# MCU_block.net
KiCad netlist of a schematic drawn in Altium Designer
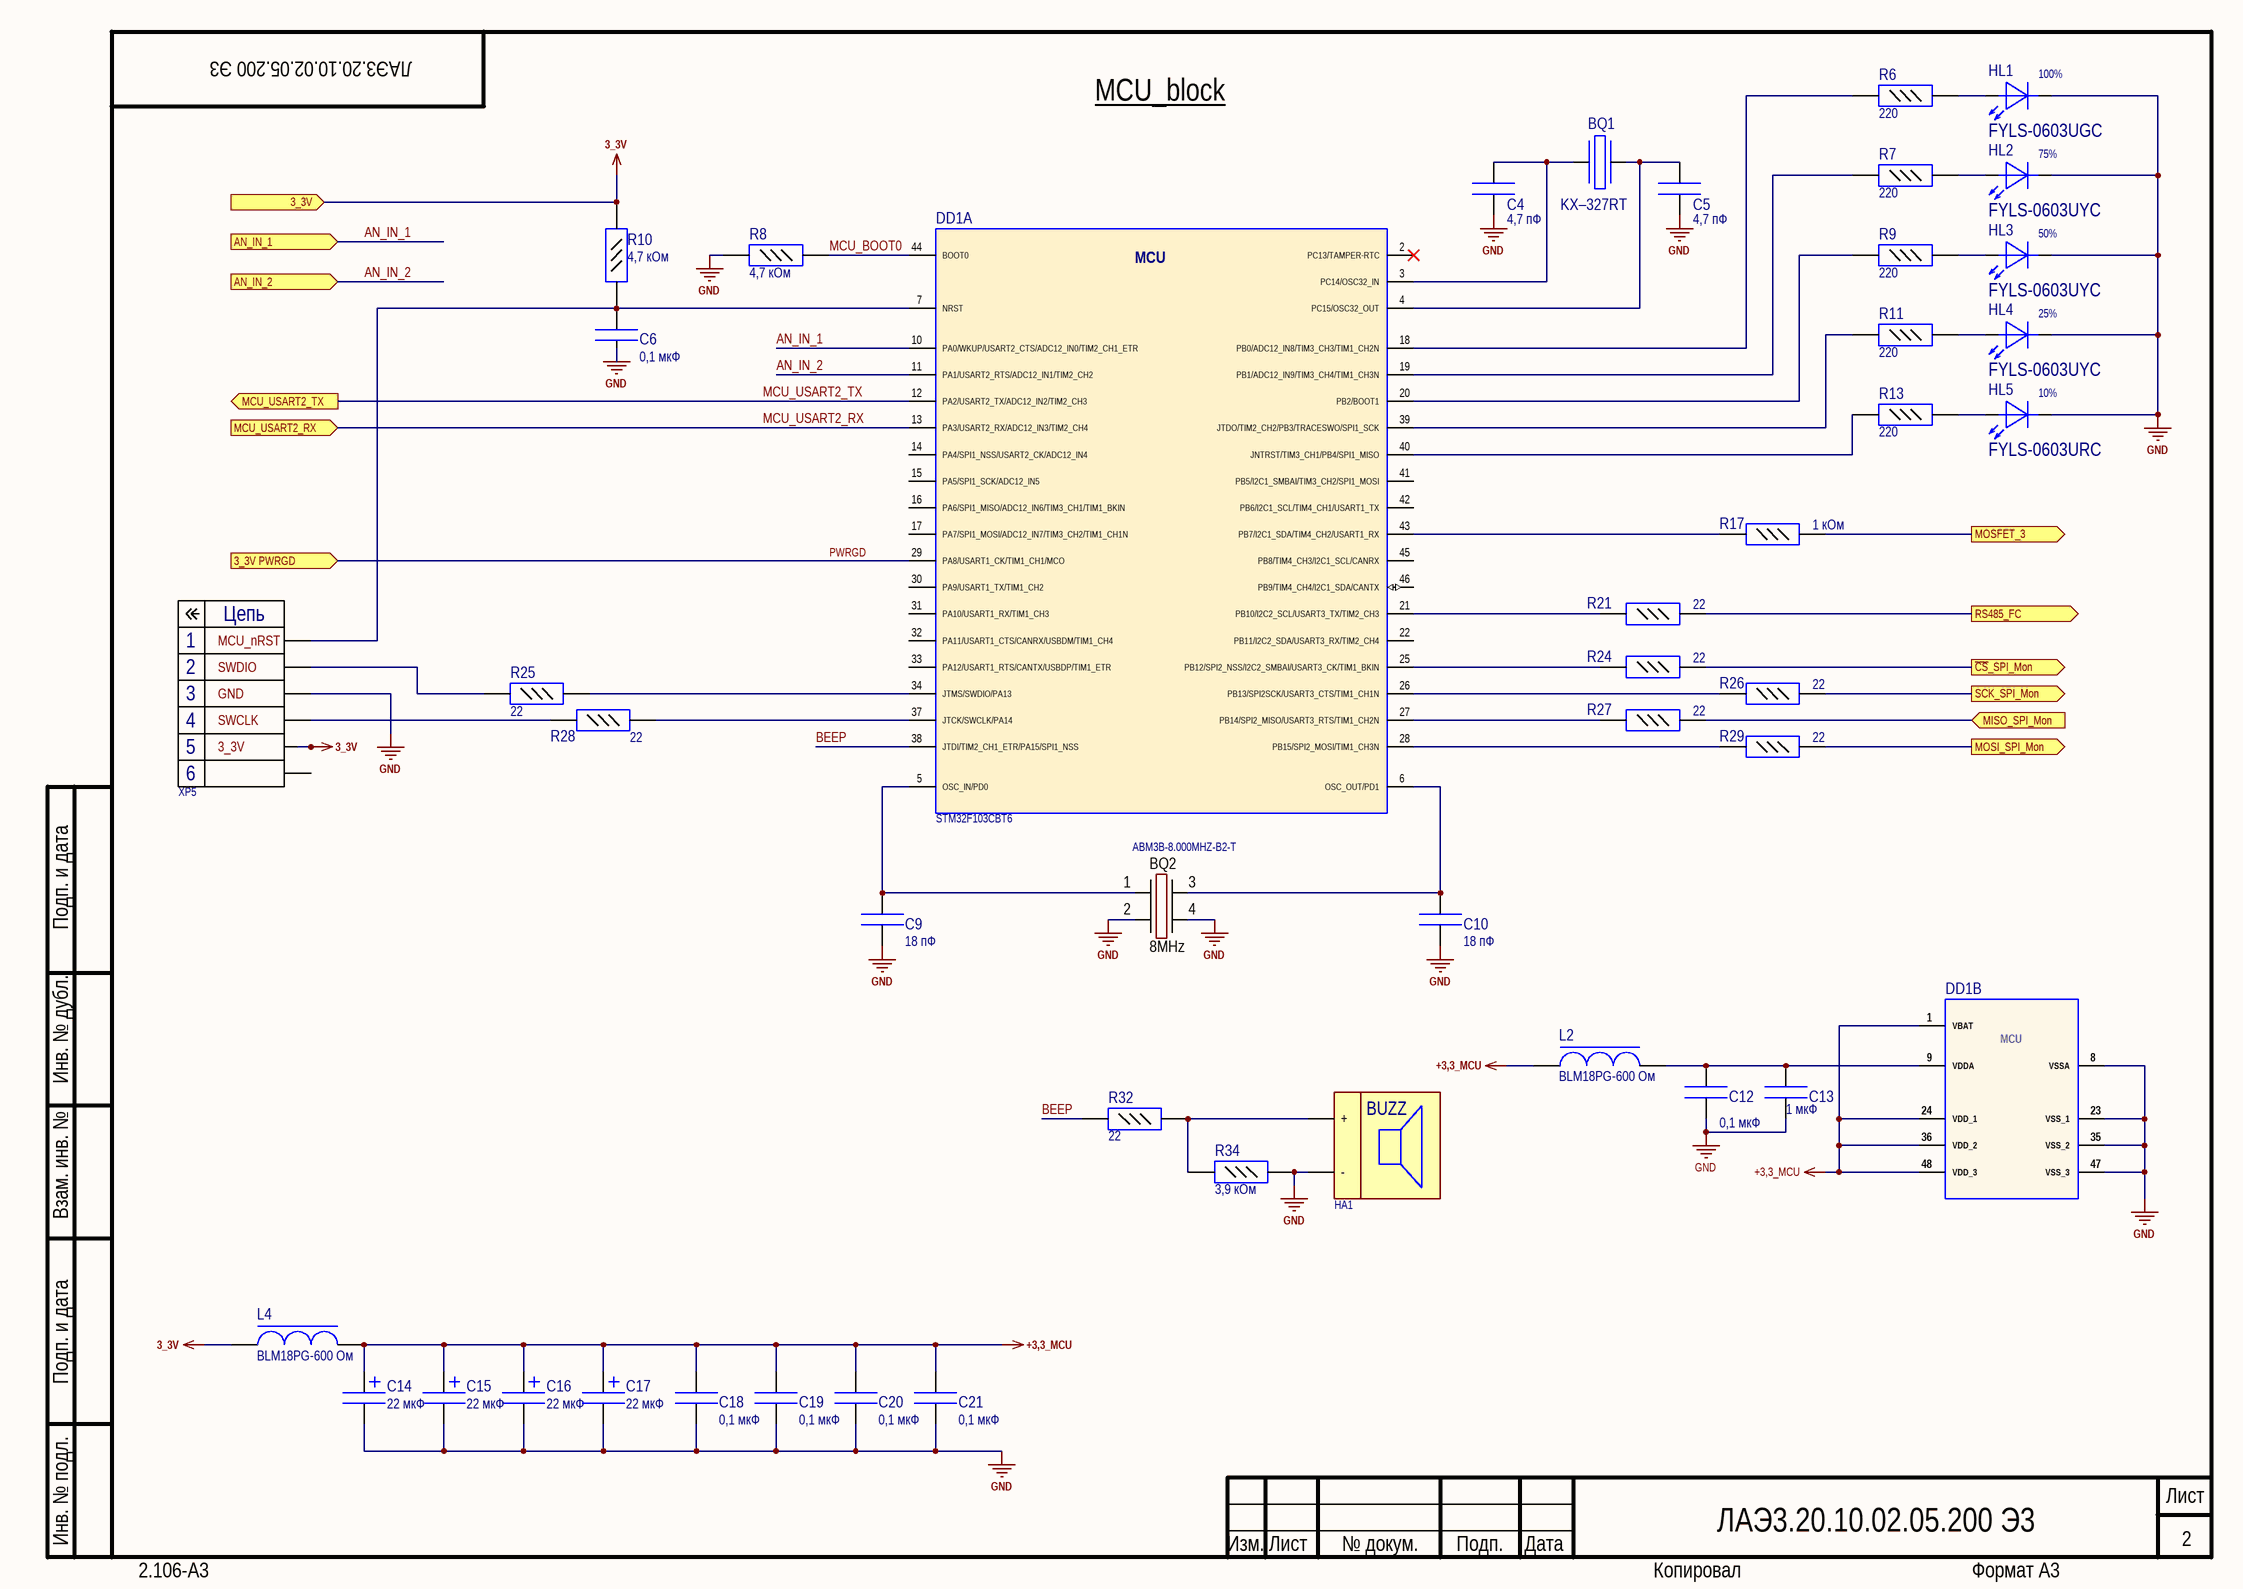
[diagram p0: MCU_block.SchDoc]

(export (version "E")
  (design (tool "Eeschema 10.0.6"))
  (components
    (comp (ref "BQ1")
      (value "KX–327RT")
      (footprint "KX–327RT")
      (description "Чип резонатор 32.768 кГц")
      (libsource (lib "Резонаторы") (part "KX–327RT"))
    )
    (comp (ref "BQ2")
      (value "ABM3B-8.000MHZ-B2-T")
      (footprint "OSC: 5032")
      (fields
        (field (name "MANUFACTURER") "Diodes Incorporated")
        (field (name "PARTNUMBER") "FY1000009")
        (field (name "VALUEMANUFACTURERPARTNUMBER") "Crystal, 8MHz, 20pF, ±30ppm, case 5032, -40...+85°C")
        (field (name "FREQUENCY") "8MHz")
        (field (name "SUPPLIER PART NUMBER 1") "ABM3B-8.000MHZ-B2-T")
      )
      (libsource (lib "Oscilator") (part "Crystal_5032"))
    )
    (comp (ref "C4")
      (value "4,7 пФ")
      (footprint "CC0603")
      (description "Чип конденсатор керамический")
      (fields (field (name "Comment") "CC0603-X5R-4,7 пФ-20%-10В"))
      (libsource (lib "Конденсаторы") (part "CC0603-X5R-#-20%-10В"))
    )
    (comp (ref "C5")
      (value "4,7 пФ")
      (footprint "CC0603")
      (description "Чип конденсатор керамический")
      (fields (field (name "Comment") "CC0603-X5R-4,7 пФ-20%-10В"))
      (libsource (lib "Конденсаторы") (part "CC0603-X5R-#-20%-10В"))
    )
    (comp (ref "C6")
      (value "0,1 мкФ")
      (footprint "CC0603")
      (description "Чип конденсатор керамический")
      (fields (field (name "Comment") "CC0603-X5R-0,1 мкФ-20%-10В"))
      (libsource (lib "Конденсаторы") (part "CC0603-X5R-#-20%-10В"))
    )
    (comp (ref "C9")
      (value "18 пФ")
      (footprint "CC0603")
      (description "Чип конденсатор керамический")
      (fields (field (name "Comment") "CC0603-X5R-18 пФ-20%-10В"))
      (libsource (lib "Конденсаторы") (part "CC0603-X5R-#-20%-10В"))
    )
    (comp (ref "C10")
      (value "18 пФ")
      (footprint "CC0603")
      (description "Чип конденсатор керамический")
      (fields (field (name "Comment") "CC0603-X5R-18 пФ-20%-10В"))
      (libsource (lib "Конденсаторы") (part "CC0603-X5R-#-20%-10В"))
    )
    (comp (ref "C12")
      (value "0,1 мкФ")
      (footprint "CC0603")
      (description "Чип конденсатор керамический")
      (fields (field (name "Comment") "CC0603-X5R-0,1 мкФ-20%-10В"))
      (libsource (lib "Конденсаторы") (part "CC0603-X5R-#-20%-10В"))
    )
    (comp (ref "C13")
      (value "1 мкФ")
      (footprint "CC0603")
      (description "Чип конденсатор керамический")
      (fields (field (name "Comment") "CC0603-X5R-1 мкФ-20%-10В"))
      (libsource (lib "Конденсаторы") (part "CC0603-X5R-#-20%-10В"))
    )
    (comp (ref "C14")
      (value "22 мкФ")
      (footprint "CT-C")
      (description "Чип конденсатор  танталовый")
      (fields (field (name "PARTNUMBER") "593D226X9016C2TE3") (field (name "Comment") "CT-10V-22uF-±20%-C"))
      (libsource (lib "Конденсаторы") (part "CT-10V-#-±20%-C"))
    )
    (comp (ref "C15")
      (value "22 мкФ")
      (footprint "CT-C")
      (description "Чип конденсатор  танталовый")
      (fields (field (name "PARTNUMBER") "593D226X9016C2TE3") (field (name "Comment") "CT-10V-22uF-±20%-C"))
      (libsource (lib "Конденсаторы") (part "CT-10V-#-±20%-C"))
    )
    (comp (ref "C16")
      (value "22 мкФ")
      (footprint "CT-C")
      (description "Чип конденсатор  танталовый")
      (fields (field (name "PARTNUMBER") "593D226X9016C2TE3") (field (name "Comment") "CT-10V-22uF-±20%-C"))
      (libsource (lib "Конденсаторы") (part "CT-10V-#-±20%-C"))
    )
    (comp (ref "C17")
      (value "22 мкФ")
      (footprint "CT-C")
      (description "Чип конденсатор  танталовый")
      (fields (field (name "PARTNUMBER") "593D226X9016C2TE3") (field (name "Comment") "CT-10V-22uF-±20%-C"))
      (libsource (lib "Конденсаторы") (part "CT-10V-#-±20%-C"))
    )
    (comp (ref "C18")
      (value "0,1 мкФ")
      (footprint "CC0603")
      (description "Чип конденсатор керамический")
      (fields (field (name "Comment") "CC0603-X5R-0,1 мкФ-20%-10В"))
      (libsource (lib "Конденсаторы") (part "CC0603-X5R-#-20%-10В"))
    )
    (comp (ref "C19")
      (value "0,1 мкФ")
      (footprint "CC0603")
      (description "Чип конденсатор керамический")
      (fields (field (name "Comment") "CC0603-X5R-0,1 мкФ-20%-10В"))
      (libsource (lib "Конденсаторы") (part "CC0603-X5R-#-20%-10В"))
    )
    (comp (ref "C20")
      (value "0,1 мкФ")
      (footprint "CC0603")
      (description "Чип конденсатор керамический")
      (fields (field (name "Comment") "CC0603-X5R-0,1 мкФ-20%-10В"))
      (libsource (lib "Конденсаторы") (part "CC0603-X5R-#-20%-10В"))
    )
    (comp (ref "C21")
      (value "0,1 мкФ")
      (footprint "CC0603")
      (description "Чип конденсатор керамический")
      (fields (field (name "Comment") "CC0603-X5R-0,1 мкФ-20%-10В"))
      (libsource (lib "Конденсаторы") (part "CC0603-X5R-#-20%-10В"))
    )
    (comp (ref "DD1")
      (value "STM32F103CBT6")
      (footprint "LQFP50P700x700-48")
      (libsource (lib "batmon_ICs") (part "STM32F103CBT6"))
    )
    (comp (ref "HA1")
      (value "HCM1203X")
      (footprint "HCM12X")
      (description "Пьезокерамический излучатель звука")
      (libsource (lib "Динамики и пищалки") (part "HCM1203X"))
    )
    (comp (ref "HL1")
      (value "FYLS-0603UGC")
      (footprint "LED0603_GREEN")
      (description "Светодиод зеленый SMD0603")
      (fields (field (name "MEAN") "100%"))
      (libsource (lib "Индикация") (part "FYLS-0603UGC"))
    )
    (comp (ref "HL2")
      (value "FYLS-0603UYC")
      (footprint "LED0603_Yellow")
      (description "Светодиод желтый SMD0603")
      (fields (field (name "MEAN") "75%"))
      (libsource (lib "Индикация") (part "FYLS-0603UYC"))
    )
    (comp (ref "HL3")
      (value "FYLS-0603UYC")
      (footprint "LED0603_Yellow")
      (description "Светодиод желтый SMD0603")
      (fields (field (name "MEAN") "50%"))
      (libsource (lib "Индикация") (part "FYLS-0603UYC"))
    )
    (comp (ref "HL4")
      (value "FYLS-0603UYC")
      (footprint "LED0603_Yellow")
      (description "Светодиод желтый SMD0603")
      (fields (field (name "MEAN") "25%"))
      (libsource (lib "Индикация") (part "FYLS-0603UYC"))
    )
    (comp (ref "HL5")
      (value "FYLS-0603URC")
      (footprint "LED0603_Red")
      (description "Светодиод красный SMD0603")
      (fields (field (name "MEAN") "10%"))
      (libsource (lib "Индикация") (part "FYLS-0603URC"))
    )
    (comp (ref "L2")
      (value "BLM18PG-600 Ом")
      (footprint "CL0603")
      (description "Чип индуктивность подавления EMP")
      (libsource (lib "Индуктивности") (part "BLM18"))
    )
    (comp (ref "L4")
      (value "BLM18PG-600 Ом")
      (footprint "CL0603")
      (description "Чип индуктивность подавления EMP")
      (libsource (lib "Индуктивности") (part "BLM18"))
    )
    (comp (ref "R6")
      (value "220")
      (footprint "CR0603")
      (description "Чип резистор")
      (fields (field (name "Comment") "CR0603-220-±5%"))
      (libsource (lib "Резисторы") (part "CR0603-#-±5%"))
    )
    (comp (ref "R7")
      (value "220")
      (footprint "CR0603")
      (description "Чип резистор")
      (fields (field (name "Comment") "CR0603-220-±5%"))
      (libsource (lib "Резисторы") (part "CR0603-#-±5%"))
    )
    (comp (ref "R8")
      (value "4,7 кОм")
      (footprint "CR0603")
      (description "Чип резистор")
      (fields (field (name "Comment") "CR0603-4,7 кОм-±5%"))
      (libsource (lib "") (part "CR0603-#-±5%_1"))
    )
    (comp (ref "R9")
      (value "220")
      (footprint "CR0603")
      (description "Чип резистор")
      (fields (field (name "Comment") "CR0603-220-±5%"))
      (libsource (lib "Резисторы") (part "CR0603-#-±5%"))
    )
    (comp (ref "R10")
      (value "4,7 кОм")
      (footprint "CR0603")
      (description "Чип резистор")
      (fields (field (name "Comment") "CR0603-4,7 кОм-±5%"))
      (libsource (lib "") (part "CR0603-#-±5%_2"))
    )
    (comp (ref "R11")
      (value "220")
      (footprint "CR0603")
      (description "Чип резистор")
      (fields (field (name "Comment") "CR0603-220-±5%"))
      (libsource (lib "Резисторы") (part "CR0603-#-±5%"))
    )
    (comp (ref "R13")
      (value "220")
      (footprint "CR0603")
      (description "Чип резистор")
      (fields (field (name "Comment") "CR0603-220-±5%"))
      (libsource (lib "Резисторы") (part "CR0603-#-±5%"))
    )
    (comp (ref "R17")
      (value "1 кОм")
      (footprint "CR0603")
      (description "Чип резистор")
      (fields (field (name "Comment") "CR0603-1 кОм-±5%"))
      (libsource (lib "Резисторы") (part "CR0603-#-±5%"))
    )
    (comp (ref "R21")
      (value "22")
      (footprint "CR0603")
      (description "Чип резистор")
      (fields (field (name "Comment") "CR0603-22-±5%"))
      (libsource (lib "Резисторы") (part "CR0603-#-±5%"))
    )
    (comp (ref "R24")
      (value "22")
      (footprint "CR0603")
      (description "Чип резистор")
      (fields (field (name "Comment") "CR0603-22-±5%"))
      (libsource (lib "Резисторы") (part "CR0603-#-±5%"))
    )
    (comp (ref "R25")
      (value "22")
      (footprint "CR0603")
      (description "Чип резистор")
      (fields (field (name "Comment") "CR0603-22-±5%"))
      (libsource (lib "Резисторы") (part "CR0603-#-±5%"))
    )
    (comp (ref "R26")
      (value "22")
      (footprint "CR0603")
      (description "Чип резистор")
      (fields (field (name "Comment") "CR0603-22-±5%"))
      (libsource (lib "Резисторы") (part "CR0603-#-±5%"))
    )
    (comp (ref "R27")
      (value "22")
      (footprint "CR0603")
      (description "Чип резистор")
      (fields (field (name "Comment") "CR0603-22-±5%"))
      (libsource (lib "Резисторы") (part "CR0603-#-±5%"))
    )
    (comp (ref "R28")
      (value "22")
      (footprint "CR0603")
      (description "Чип резистор")
      (fields (field (name "Comment") "CR0603-22-±5%"))
      (libsource (lib "Резисторы") (part "CR0603-#-±5%"))
    )
    (comp (ref "R29")
      (value "22")
      (footprint "CR0603")
      (description "Чип резистор")
      (fields (field (name "Comment") "CR0603-22-±5%"))
      (libsource (lib "Резисторы") (part "CR0603-#-±5%"))
    )
    (comp (ref "R32")
      (value "22")
      (footprint "CR0603")
      (description "Чип резистор")
      (fields (field (name "Comment") "CR0603-22-±5%"))
      (libsource (lib "Резисторы") (part "CR0603-#-±5%"))
    )
    (comp (ref "R34")
      (value "3,9 кОм")
      (footprint "CR0603")
      (description "Чип резистор")
      (fields (field (name "Comment") "CR0603-3,9 кОм-±5%"))
      (libsource (lib "") (part "CR0603-#-±5%_1"))
    )
    (comp (ref "XP5")
      (value "DS1022-1x6R")
      (footprint "PLS-6R")
      (description "Штыри на плату однорядные угловые")
      (libsource (lib "batmon_ICs") (part "PLS-6R"))
    )
  )
  (nets
    (net (code "1") (name "+3,3_MCU") (class "Default")
      (node (ref "C14") (pin "1") (pinfunction "+_1") (pintype "passive"))
      (node (ref "C15") (pin "1") (pinfunction "+_1") (pintype "passive"))
      (node (ref "C16") (pin "1") (pinfunction "+_1") (pintype "passive"))
      (node (ref "C17") (pin "1") (pinfunction "+_1") (pintype "passive"))
      (node (ref "C18") (pin "1") (pinfunction "+_1") (pintype "passive"))
      (node (ref "C19") (pin "1") (pinfunction "+_1") (pintype "passive"))
      (node (ref "C20") (pin "1") (pinfunction "+_1") (pintype "passive"))
      (node (ref "C21") (pin "1") (pinfunction "+_1") (pintype "passive"))
      (node (ref "DD1") (pin "1") (pinfunction "VBAT_1") (pintype "power_in"))
      (node (ref "DD1") (pin "24") (pinfunction "VDD_1_24") (pintype "power_in"))
      (node (ref "DD1") (pin "36") (pinfunction "VDD_2_36") (pintype "power_in"))
      (node (ref "DD1") (pin "48") (pinfunction "VDD_3_48") (pintype "power_in"))
      (node (ref "L2") (pin "1") (pinfunction "1_1") (pintype "passive"))
      (node (ref "L4") (pin "2") (pinfunction "2_2") (pintype "passive"))
    )
    (net (code "2") (name "/AN_IN_1") (class "Default")
      (node (ref "DD1") (pin "10") (pinfunction "PA0/WKUP/USART2_CTS/ADC12_IN0/TIM2_CH1_ETR_10") (pintype "passive"))
    )
    (net (code "3") (name "/AN_IN_2") (class "Default")
      (node (ref "DD1") (pin "11") (pinfunction "PA1/USART2_RTS/ADC12_IN1/TIM2_CH2_11") (pintype "passive"))
    )
    (net (code "4") (name "/BEEP") (class "Default")
      (node (ref "DD1") (pin "38") (pinfunction "JTDI/TIM2_CH1_ETR/PA15/SPI1_NSS_38") (pintype "passive"))
      (node (ref "R32") (pin "1") (pinfunction "+_1") (pintype "passive"))
    )
    (net (code "5") (name "/MCU_BOOT0") (class "Default")
      (node (ref "DD1") (pin "44") (pinfunction "BOOT0_44") (pintype "passive"))
      (node (ref "R8") (pin "1") (pinfunction "+_1") (pintype "passive"))
    )
    (net (code "6") (name "/MCU_USART2_RX") (class "Default")
      (node (ref "DD1") (pin "13") (pinfunction "PA3/USART2_RX/ADC12_IN3/TIM2_CH4_13") (pintype "passive"))
    )
    (net (code "7") (name "/MCU_USART2_TX") (class "Default")
      (node (ref "DD1") (pin "12") (pinfunction "PA2/USART2_TX/ADC12_IN2/TIM2_CH3_12") (pintype "passive"))
    )
    (net (code "9") (name "/MISO_SPI_Mon") (class "Default")
      (node (ref "R27") (pin "2") (pinfunction "-_2") (pintype "passive"))
    )
    (net (code "10") (name "/MOSFET_3") (class "Default")
      (node (ref "R17") (pin "2") (pinfunction "-_2") (pintype "passive"))
    )
    (net (code "11") (name "/MOSI_SPI_Mon") (class "Default")
      (node (ref "R29") (pin "2") (pinfunction "-_2") (pintype "passive"))
    )
    (net (code "12") (name "/PWRGD") (class "Default")
      (node (ref "DD1") (pin "29") (pinfunction "PA8/USART1_CK/TIM1_CH1/MCO_29") (pintype "passive"))
    )
    (net (code "13") (name "/RS485_FC") (class "Default")
      (node (ref "R21") (pin "2") (pinfunction "-_2") (pintype "passive"))
    )
    (net (code "14") (name "/SCK_SPI_Mon") (class "Default")
      (node (ref "R26") (pin "2") (pinfunction "-_2") (pintype "passive"))
    )
    (net (code "17") (name "/~{CS}_SPI_Mon") (class "Default")
      (node (ref "R24") (pin "2") (pinfunction "-_2") (pintype "passive"))
    )
    (net (code "18") (name "3_3V") (class "Default")
      (node (ref "L4") (pin "1") (pinfunction "1_1") (pintype "passive"))
      (node (ref "R10") (pin "2") (pinfunction "-_2") (pintype "passive"))
      (node (ref "XP5") (pin "5") (pinfunction "5_5") (pintype "passive"))
    )
    (net (code "19") (name "GND") (class "Default")
      (node (ref "BQ2") (pin "2") (pinfunction "2_2") (pintype "passive"))
      (node (ref "BQ2") (pin "4") (pinfunction "4_4") (pintype "passive"))
      (node (ref "C10") (pin "2") (pinfunction "-_2") (pintype "passive"))
      (node (ref "C12") (pin "2") (pinfunction "-_2") (pintype "passive"))
      (node (ref "C13") (pin "2") (pinfunction "-_2") (pintype "passive"))
      (node (ref "C14") (pin "2") (pinfunction "-_2") (pintype "passive"))
      (node (ref "C15") (pin "2") (pinfunction "-_2") (pintype "passive"))
      (node (ref "C16") (pin "2") (pinfunction "-_2") (pintype "passive"))
      (node (ref "C17") (pin "2") (pinfunction "-_2") (pintype "passive"))
      (node (ref "C18") (pin "2") (pinfunction "-_2") (pintype "passive"))
      (node (ref "C19") (pin "2") (pinfunction "-_2") (pintype "passive"))
      (node (ref "C20") (pin "2") (pinfunction "-_2") (pintype "passive"))
      (node (ref "C21") (pin "2") (pinfunction "-_2") (pintype "passive"))
      (node (ref "C4") (pin "2") (pinfunction "-_2") (pintype "passive"))
      (node (ref "C5") (pin "2") (pinfunction "-_2") (pintype "passive"))
      (node (ref "C6") (pin "2") (pinfunction "-_2") (pintype "passive"))
      (node (ref "C9") (pin "2") (pinfunction "-_2") (pintype "passive"))
      (node (ref "DD1") (pin "23") (pinfunction "VSS_1_23") (pintype "power_in"))
      (node (ref "DD1") (pin "35") (pinfunction "VSS_2_35") (pintype "power_in"))
      (node (ref "DD1") (pin "47") (pinfunction "VSS_3_47") (pintype "power_in"))
      (node (ref "DD1") (pin "8") (pinfunction "VSSA_8") (pintype "power_in"))
      (node (ref "HA1") (pin "2") (pinfunction "-_2") (pintype "passive"))
      (node (ref "HL1") (pin "2") (pinfunction "K_2") (pintype "passive"))
      (node (ref "HL2") (pin "2") (pinfunction "K_2") (pintype "passive"))
      (node (ref "HL3") (pin "2") (pinfunction "K_2") (pintype "passive"))
      (node (ref "HL4") (pin "2") (pinfunction "K_2") (pintype "passive"))
      (node (ref "HL5") (pin "2") (pinfunction "K_2") (pintype "passive"))
      (node (ref "R34") (pin "1") (pinfunction "+_1") (pintype "passive"))
      (node (ref "R8") (pin "2") (pinfunction "-_2") (pintype "passive"))
      (node (ref "XP5") (pin "3") (pinfunction "3_3") (pintype "passive"))
    )
    (net (code "20") (name "Net-(C4-+)") (class "Default")
      (node (ref "BQ1") (pin "1") (pintype "passive"))
      (node (ref "C4") (pin "1") (pinfunction "+_1") (pintype "passive"))
      (node (ref "DD1") (pin "3") (pinfunction "PC14/OSC32_IN_3") (pintype "passive"))
    )
    (net (code "21") (name "Net-(C5-+)") (class "Default")
      (node (ref "BQ1") (pin "2") (pintype "passive"))
      (node (ref "C5") (pin "1") (pinfunction "+_1") (pintype "passive"))
      (node (ref "DD1") (pin "4") (pinfunction "PC15/OSC32_OUT_4") (pintype "passive"))
    )
    (net (code "22") (name "Net-(C6-+)") (class "Default")
      (node (ref "C6") (pin "1") (pinfunction "+_1") (pintype "passive"))
      (node (ref "DD1") (pin "7") (pinfunction "NRST_7") (pintype "passive"))
      (node (ref "R10") (pin "1") (pinfunction "+_1") (pintype "passive"))
      (node (ref "XP5") (pin "1") (pinfunction "1_1") (pintype "passive"))
    )
    (net (code "23") (name "Net-(C9-+)") (class "Default")
      (node (ref "BQ2") (pin "1") (pinfunction "1_1") (pintype "passive"))
      (node (ref "C9") (pin "1") (pinfunction "+_1") (pintype "passive"))
      (node (ref "DD1") (pin "5") (pinfunction "OSC_IN/PD0_5") (pintype "passive"))
    )
    (net (code "24") (name "Net-(C10-+)") (class "Default")
      (node (ref "BQ2") (pin "3") (pinfunction "3_3") (pintype "passive"))
      (node (ref "C10") (pin "1") (pinfunction "+_1") (pintype "passive"))
      (node (ref "DD1") (pin "6") (pinfunction "OSC_OUT/PD1_6") (pintype "passive"))
    )
    (net (code "25") (name "Net-(C12-+)") (class "Default")
      (node (ref "C12") (pin "1") (pinfunction "+_1") (pintype "passive"))
      (node (ref "C13") (pin "1") (pinfunction "+_1") (pintype "passive"))
      (node (ref "DD1") (pin "9") (pinfunction "VDDA_9") (pintype "power_in"))
      (node (ref "L2") (pin "2") (pinfunction "2_2") (pintype "passive"))
    )
    (net (code "26") (name "Net-(DD1A-JNTRST{slash}TIM3_CH1{slash}PB4{slash}SPI1_MISO)") (class "Default")
      (node (ref "DD1") (pin "40") (pinfunction "JNTRST/TIM3_CH1/PB4/SPI1_MISO_40") (pintype "passive"))
      (node (ref "R13") (pin "1") (pinfunction "+_1") (pintype "passive"))
    )
    (net (code "27") (name "Net-(DD1A-JTCK{slash}SWCLK{slash}PA14)") (class "Default")
      (node (ref "DD1") (pin "37") (pinfunction "JTCK/SWCLK/PA14_37") (pintype "passive"))
      (node (ref "R28") (pin "2") (pinfunction "-_2") (pintype "passive"))
    )
    (net (code "28") (name "Net-(DD1A-JTDO{slash}TIM2_CH2{slash}PB3{slash}TRACESWO{slash}SPI1_SCK)") (class "Default")
      (node (ref "DD1") (pin "39") (pinfunction "JTDO/TIM2_CH2/PB3/TRACESWO/SPI1_SCK_39") (pintype "passive"))
      (node (ref "R11") (pin "1") (pinfunction "+_1") (pintype "passive"))
    )
    (net (code "29") (name "Net-(DD1A-JTMS{slash}SWDIO{slash}PA13)") (class "Default")
      (node (ref "DD1") (pin "34") (pinfunction "JTMS/SWDIO/PA13_34") (pintype "passive"))
      (node (ref "R25") (pin "2") (pinfunction "-_2") (pintype "passive"))
    )
    (net (code "30") (name "Net-(DD1A-PB0{slash}ADC12_IN8{slash}TIM3_CH3{slash}TIM1_CH2N)") (class "Default")
      (node (ref "DD1") (pin "18") (pinfunction "PB0/ADC12_IN8/TIM3_CH3/TIM1_CH2N_18") (pintype "passive"))
      (node (ref "R6") (pin "1") (pinfunction "+_1") (pintype "passive"))
    )
    (net (code "31") (name "Net-(DD1A-PB1{slash}ADC12_IN9{slash}TIM3_CH4{slash}TIM1_CH3N)") (class "Default")
      (node (ref "DD1") (pin "19") (pinfunction "PB1/ADC12_IN9/TIM3_CH4/TIM1_CH3N_19") (pintype "passive"))
      (node (ref "R7") (pin "1") (pinfunction "+_1") (pintype "passive"))
    )
    (net (code "32") (name "Net-(DD1A-PB2{slash}BOOT1)") (class "Default")
      (node (ref "DD1") (pin "20") (pinfunction "PB2/BOOT1_20") (pintype "passive"))
      (node (ref "R9") (pin "1") (pinfunction "+_1") (pintype "passive"))
    )
    (net (code "33") (name "Net-(DD1A-PB7{slash}I2C1_SDA{slash}TIM4_CH2{slash}USART1_RX)") (class "Default")
      (node (ref "DD1") (pin "43") (pinfunction "PB7/I2C1_SDA/TIM4_CH2/USART1_RX_43") (pintype "passive"))
      (node (ref "R17") (pin "1") (pinfunction "+_1") (pintype "passive"))
    )
    (net (code "34") (name "Net-(DD1A-PB10{slash}I2C2_SCL{slash}USART3_TX{slash}TIM2_CH3)") (class "Default")
      (node (ref "DD1") (pin "21") (pinfunction "PB10/I2C2_SCL/USART3_TX/TIM2_CH3_21") (pintype "passive"))
      (node (ref "R21") (pin "1") (pinfunction "+_1") (pintype "passive"))
    )
    (net (code "35") (name "Net-(DD1A-PB12{slash}SPI2_NSS{slash}I2C2_SMBAI{slash}USART3_CK{slash}TIM1_BKIN)") (class "Default")
      (node (ref "DD1") (pin "25") (pinfunction "PB12/SPI2_NSS/I2C2_SMBAI/USART3_CK/TIM1_BKIN_25") (pintype "passive"))
      (node (ref "R24") (pin "1") (pinfunction "+_1") (pintype "passive"))
    )
    (net (code "36") (name "Net-(DD1A-PB13{slash}SPI2SCK{slash}USART3_CTS{slash}TIM1_CH1N)") (class "Default")
      (node (ref "DD1") (pin "26") (pinfunction "PB13/SPI2SCK/USART3_CTS/TIM1_CH1N_26") (pintype "passive"))
      (node (ref "R26") (pin "1") (pinfunction "+_1") (pintype "passive"))
    )
    (net (code "37") (name "Net-(DD1A-PB14{slash}SPI2_MISO{slash}USART3_RTS{slash}TIM1_CH2N)") (class "Default")
      (node (ref "DD1") (pin "27") (pinfunction "PB14/SPI2_MISO/USART3_RTS/TIM1_CH2N_27") (pintype "passive"))
      (node (ref "R27") (pin "1") (pinfunction "+_1") (pintype "passive"))
    )
    (net (code "38") (name "Net-(DD1A-PB15{slash}SPI2_MOSI{slash}TIM1_CH3N)") (class "Default")
      (node (ref "DD1") (pin "28") (pinfunction "PB15/SPI2_MOSI/TIM1_CH3N_28") (pintype "passive"))
      (node (ref "R29") (pin "1") (pinfunction "+_1") (pintype "passive"))
    )
    (net (code "39") (name "Net-(HA1-+)") (class "Default")
      (node (ref "HA1") (pin "1") (pinfunction "+_1") (pintype "passive"))
      (node (ref "R32") (pin "2") (pinfunction "-_2") (pintype "passive"))
      (node (ref "R34") (pin "2") (pinfunction "-_2") (pintype "passive"))
    )
    (net (code "40") (name "Net-(HL1-A)") (class "Default")
      (node (ref "HL1") (pin "1") (pinfunction "A_1") (pintype "passive"))
      (node (ref "R6") (pin "2") (pinfunction "-_2") (pintype "passive"))
    )
    (net (code "41") (name "Net-(HL2-A)") (class "Default")
      (node (ref "HL2") (pin "1") (pinfunction "A_1") (pintype "passive"))
      (node (ref "R7") (pin "2") (pinfunction "-_2") (pintype "passive"))
    )
    (net (code "42") (name "Net-(HL3-A)") (class "Default")
      (node (ref "HL3") (pin "1") (pinfunction "A_1") (pintype "passive"))
      (node (ref "R9") (pin "2") (pinfunction "-_2") (pintype "passive"))
    )
    (net (code "43") (name "Net-(HL4-A)") (class "Default")
      (node (ref "HL4") (pin "1") (pinfunction "A_1") (pintype "passive"))
      (node (ref "R11") (pin "2") (pinfunction "-_2") (pintype "passive"))
    )
    (net (code "44") (name "Net-(HL5-A)") (class "Default")
      (node (ref "HL5") (pin "1") (pinfunction "A_1") (pintype "passive"))
      (node (ref "R13") (pin "2") (pinfunction "-_2") (pintype "passive"))
    )
    (net (code "45") (name "Net-(R25-+)") (class "Default")
      (node (ref "R25") (pin "1") (pinfunction "+_1") (pintype "passive"))
      (node (ref "XP5") (pin "2") (pinfunction "2_2") (pintype "passive"))
    )
    (net (code "46") (name "Net-(R28-+)") (class "Default")
      (node (ref "R28") (pin "1") (pinfunction "+_1") (pintype "passive"))
      (node (ref "XP5") (pin "4") (pinfunction "4_4") (pintype "passive"))
    )
    (net (code "47") (name "unconnected-(DD1A-PA4{slash}SPI1_NSS{slash}USART2_CK{slash}ADC12_IN4-Pad14)") (class "Default")
      (node (ref "DD1") (pin "14") (pinfunction "PA4/SPI1_NSS/USART2_CK/ADC12_IN4_14") (pintype "passive"))
    )
    (net (code "48") (name "unconnected-(DD1A-PA5{slash}SPI1_SCK{slash}ADC12_IN5-Pad15)") (class "Default")
      (node (ref "DD1") (pin "15") (pinfunction "PA5/SPI1_SCK/ADC12_IN5_15") (pintype "passive"))
    )
    (net (code "49") (name "unconnected-(DD1A-PA6{slash}SPI1_MISO{slash}ADC12_IN6{slash}TIM3_CH1{slash}TIM1_BKIN-Pad16)") (class "Default")
      (node (ref "DD1") (pin "16") (pinfunction "PA6/SPI1_MISO/ADC12_IN6/TIM3_CH1/TIM1_BKIN_16") (pintype "passive"))
    )
    (net (code "50") (name "unconnected-(DD1A-PA7{slash}SPI1_MOSI{slash}ADC12_IN7{slash}TIM3_CH2{slash}TIM1_CH1N-Pad17)") (class "Default")
      (node (ref "DD1") (pin "17") (pinfunction "PA7/SPI1_MOSI/ADC12_IN7/TIM3_CH2/TIM1_CH1N_17") (pintype "passive"))
    )
    (net (code "51") (name "unconnected-(DD1A-PA9{slash}USART1_TX{slash}TIM1_CH2-Pad30)") (class "Default")
      (node (ref "DD1") (pin "30") (pinfunction "PA9/USART1_TX/TIM1_CH2_30") (pintype "passive"))
    )
    (net (code "52") (name "unconnected-(DD1A-PA10{slash}USART1_RX{slash}TIM1_CH3-Pad31)") (class "Default")
      (node (ref "DD1") (pin "31") (pinfunction "PA10/USART1_RX/TIM1_CH3_31") (pintype "passive"))
    )
    (net (code "53") (name "unconnected-(DD1A-PA11{slash}USART1_CTS{slash}CANRX{slash}USBDM{slash}TIM1_CH4-Pad32)") (class "Default")
      (node (ref "DD1") (pin "32") (pinfunction "PA11/USART1_CTS/CANRX/USBDM/TIM1_CH4_32") (pintype "passive"))
    )
    (net (code "54") (name "unconnected-(DD1A-PA12{slash}USART1_RTS{slash}CANTX{slash}USBDP{slash}TIM1_ETR-Pad33)") (class "Default")
      (node (ref "DD1") (pin "33") (pinfunction "PA12/USART1_RTS/CANTX/USBDP/TIM1_ETR_33") (pintype "passive"))
    )
    (net (code "55") (name "unconnected-(DD1A-PB5{slash}I2C1_SMBAI{slash}TIM3_CH2{slash}SPI1_MOSI-Pad41)") (class "Default")
      (node (ref "DD1") (pin "41") (pinfunction "PB5/I2C1_SMBAI/TIM3_CH2/SPI1_MOSI_41") (pintype "passive"))
    )
    (net (code "56") (name "unconnected-(DD1A-PB6{slash}I2C1_SCL{slash}TIM4_CH1{slash}USART1_TX-Pad42)") (class "Default")
      (node (ref "DD1") (pin "42") (pinfunction "PB6/I2C1_SCL/TIM4_CH1/USART1_TX_42") (pintype "passive"))
    )
    (net (code "57") (name "unconnected-(DD1A-PB8{slash}TIM4_CH3{slash}I2C1_SCL{slash}CANRX-Pad45)") (class "Default")
      (node (ref "DD1") (pin "45") (pinfunction "PB8/TIM4_CH3/I2C1_SCL/CANRX_45") (pintype "passive"))
    )
    (net (code "58") (name "unconnected-(DD1A-PB9{slash}TIM4_CH4{slash}I2C1_SDA{slash}CANTX-Pad46)") (class "Default")
      (node (ref "DD1") (pin "46") (pinfunction "PB9/TIM4_CH4/I2C1_SDA/CANTX_46") (pintype "bidirectional"))
    )
    (net (code "59") (name "unconnected-(DD1A-PB11{slash}I2C2_SDA{slash}USART3_RX{slash}TIM2_CH4-Pad22)") (class "Default")
      (node (ref "DD1") (pin "22") (pinfunction "PB11/I2C2_SDA/USART3_RX/TIM2_CH4_22") (pintype "passive"))
    )
    (net (code "60") (name "unconnected-(DD1A-PC13{slash}TAMPER-RTC-Pad2)") (class "Default")
      (node (ref "DD1") (pin "2") (pinfunction "PC13/TAMPER-RTC_2") (pintype "passive+no_connect"))
    )
    (net (code "61") (name "unconnected-(XP5-Pad6)") (class "Default")
      (node (ref "XP5") (pin "6") (pinfunction "6_6") (pintype "passive"))
    )
  )
)
